# FPGA_CONFIG.net
KiCad netlist of a schematic drawn in Altium Designer
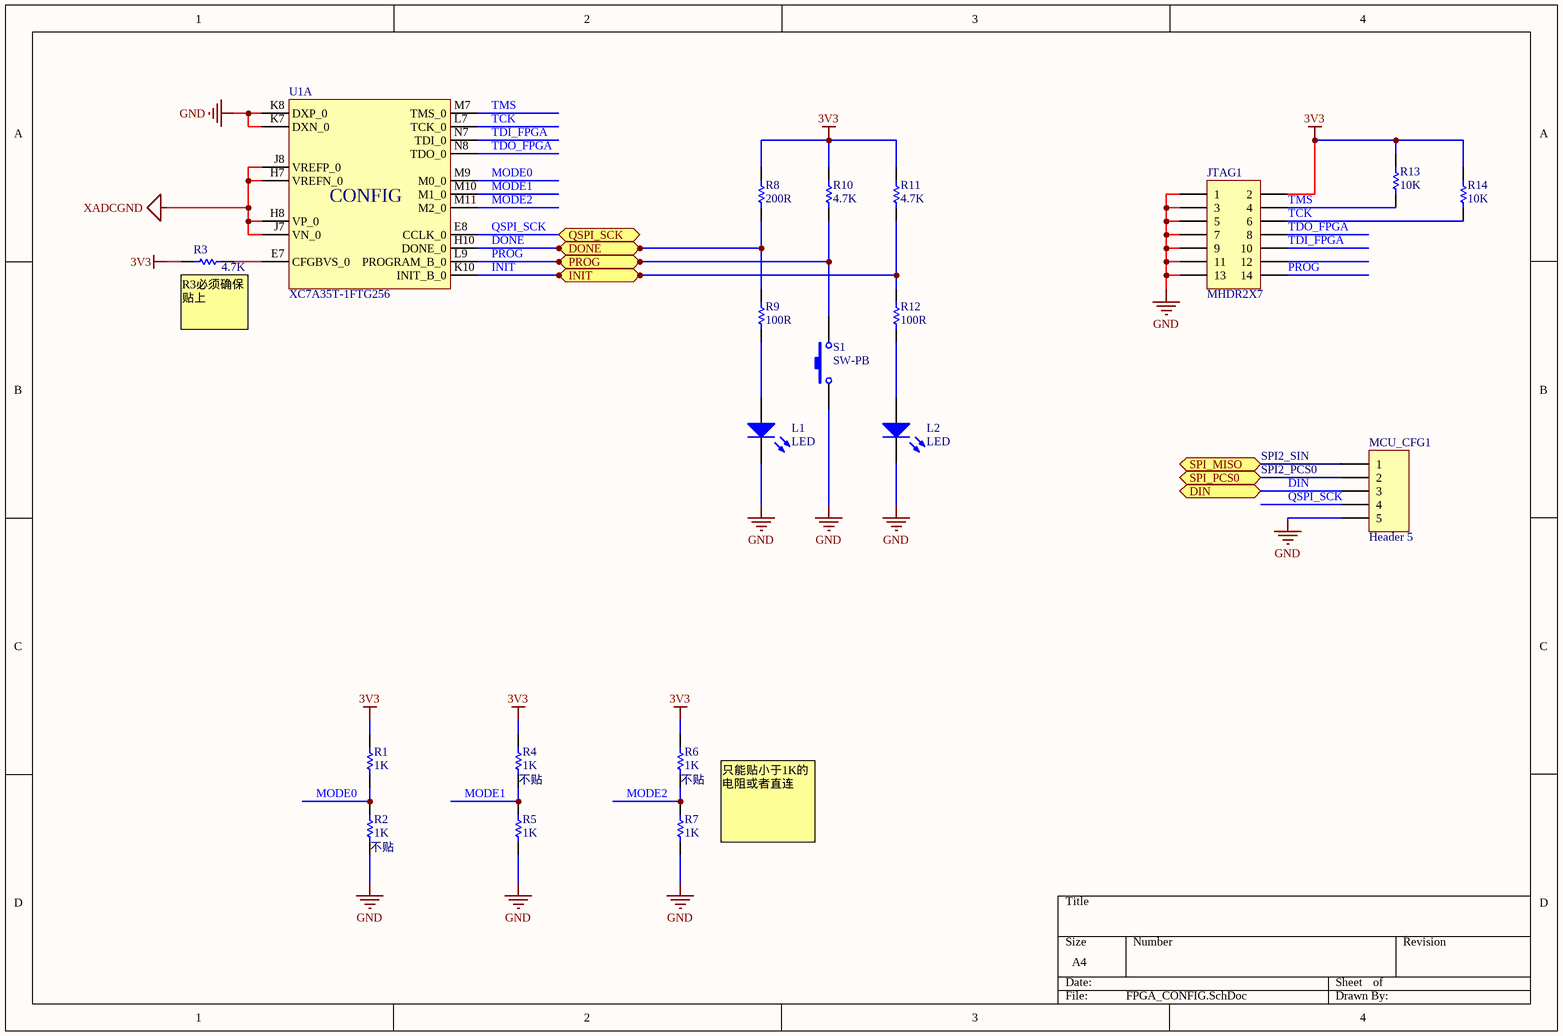
[diagram p0: FPGA_CONFIG.SchDoc]

(export (version "E")
  (design (tool "Eeschema 10.0.6"))
  (components
    (comp (ref "JTAG1")
      (value "MHDR2X7")
      (footprint "Hearder2 7X2")
      (description "Header, 7-Pin, Dual row")
      (fields (field (name "PUBLISHER") "Altium Limited"))
      (libsource (lib "Miscellaneous Connectors") (part "MHDR2X7"))
    )
    (comp (ref "L1") (value "LED") (footprint "1608[0603]") (libsource (lib "Sparks") (part "LED")))
    (comp (ref "L2") (value "LED") (footprint "1608[0603]") (libsource (lib "Sparks") (part "LED")))
    (comp (ref "MCU_CFG1")
      (value "Header 5")
      (footprint "MHDR1X5")
      (description "Header, 5-Pin")
      (fields (field (name "PUBLISHER") "Altium Limited"))
      (libsource (lib "Sparks") (part "Header 5"))
    )
    (comp (ref "R1")
      (value "1K")
      (footprint "1608[0603]")
      (description "贴片电阻")
      (fields (field (name "Comment") "Res") (field (name "PUBLISHER") "Altium Limited"))
      (libsource (lib "Sparks") (part "Res"))
    )
    (comp (ref "R2")
      (value "不贴")
      (footprint "1608[0603]")
      (description "贴片电阻")
      (fields (field (name "ALTIUM_VALUE") "1K") (field (name "PUBLISHER") "Altium Limited"))
      (libsource (lib "Sparks") (part "Res"))
    )
    (comp (ref "R3")
      (value "4.7K")
      (footprint "0402")
      (description "贴片电阻")
      (fields (field (name "Comment") "Res") (field (name "PUBLISHER") "Altium Limited"))
      (libsource (lib "Sparks") (part "Res"))
    )
    (comp (ref "R4")
      (value "不贴")
      (footprint "1608[0603]")
      (description "贴片电阻")
      (fields (field (name "ALTIUM_VALUE") "1K") (field (name "PUBLISHER") "Altium Limited"))
      (libsource (lib "Sparks") (part "Res"))
    )
    (comp (ref "R5")
      (value "1K")
      (footprint "1608[0603]")
      (description "贴片电阻")
      (fields (field (name "Comment") "Res") (field (name "PUBLISHER") "Altium Limited"))
      (libsource (lib "Sparks") (part "Res"))
    )
    (comp (ref "R6")
      (value "不贴")
      (footprint "1608[0603]")
      (description "贴片电阻")
      (fields (field (name "ALTIUM_VALUE") "1K") (field (name "PUBLISHER") "Altium Limited"))
      (libsource (lib "Sparks") (part "Res"))
    )
    (comp (ref "R7")
      (value "1K")
      (footprint "1608[0603]")
      (description "贴片电阻")
      (fields (field (name "Comment") "Res") (field (name "PUBLISHER") "Altium Limited"))
      (libsource (lib "Sparks") (part "Res"))
    )
    (comp (ref "R8")
      (value "200R")
      (footprint "1608[0603]")
      (description "贴片电阻")
      (fields (field (name "Comment") "Res") (field (name "PUBLISHER") "Altium Limited"))
      (libsource (lib "Sparks") (part "Res"))
    )
    (comp (ref "R9")
      (value "100R")
      (footprint "1608[0603]")
      (description "贴片电阻")
      (fields (field (name "Comment") "Res") (field (name "PUBLISHER") "Altium Limited"))
      (libsource (lib "Sparks") (part "Res"))
    )
    (comp (ref "R10")
      (value "4.7K")
      (footprint "1608[0603]")
      (description "贴片电阻")
      (fields (field (name "Comment") "Res") (field (name "PUBLISHER") "Altium Limited"))
      (libsource (lib "Sparks") (part "Res"))
    )
    (comp (ref "R11")
      (value "4.7K")
      (footprint "1608[0603]")
      (description "贴片电阻")
      (fields (field (name "Comment") "Res") (field (name "PUBLISHER") "Altium Limited"))
      (libsource (lib "Sparks") (part "Res"))
    )
    (comp (ref "R12")
      (value "100R")
      (footprint "1608[0603]")
      (description "贴片电阻")
      (fields (field (name "Comment") "Res") (field (name "PUBLISHER") "Altium Limited"))
      (libsource (lib "Sparks") (part "Res"))
    )
    (comp (ref "R13")
      (value "10K")
      (footprint "1608[0603]")
      (description "贴片电阻")
      (fields (field (name "Comment") "Res") (field (name "PUBLISHER") "Altium Limited"))
      (libsource (lib "Sparks") (part "Res"))
    )
    (comp (ref "R14")
      (value "10K")
      (footprint "1608[0603]")
      (description "贴片电阻")
      (fields (field (name "Comment") "Res") (field (name "PUBLISHER") "Altium Limited"))
      (libsource (lib "Sparks") (part "Res"))
    )
    (comp (ref "S1")
      (value "SW-PB")
      (footprint "key 3*4*2")
      (description "Switch")
      (fields (field (name "PUBLISHER") "Altium Limited"))
      (libsource (lib "Miscellaneous Devices") (part "SW-PB"))
    )
    (comp (ref "U1")
      (value "XC7A35T-1FTG256")
      (footprint "BGA100P9X9-81A")
      (libsource (lib "Schlib") (part "XC7A35T-1FTG256"))
    )
  )
  (nets
    (net (code "1") (name "/DIN") (class "Default")
      (node (ref "MCU_CFG1") (pin "3") (pinfunction "3_3") (pintype "passive"))
    )
    (net (code "2") (name "/DONE") (class "Default")
      (node (ref "R8") (pin "1") (pinfunction "1_1") (pintype "passive"))
      (node (ref "R9") (pin "2") (pinfunction "2_2") (pintype "passive"))
      (node (ref "U1") (pin "H10") (pinfunction "DONE_0_H10") (pintype "passive"))
    )
    (net (code "3") (name "/INIT") (class "Default")
      (node (ref "R11") (pin "1") (pinfunction "1_1") (pintype "passive"))
      (node (ref "R12") (pin "2") (pinfunction "2_2") (pintype "passive"))
      (node (ref "U1") (pin "K10") (pinfunction "INIT_B_0_K10") (pintype "passive"))
    )
    (net (code "4") (name "/MODE0") (class "Default")
      (node (ref "R1") (pin "1") (pinfunction "1_1") (pintype "passive"))
      (node (ref "R2") (pin "2") (pinfunction "2_2") (pintype "passive"))
      (node (ref "U1") (pin "M9") (pinfunction "M0_0_M9") (pintype "passive"))
    )
    (net (code "5") (name "/MODE1") (class "Default")
      (node (ref "R4") (pin "1") (pinfunction "1_1") (pintype "passive"))
      (node (ref "R5") (pin "2") (pinfunction "2_2") (pintype "passive"))
      (node (ref "U1") (pin "M10") (pinfunction "M1_0_M10") (pintype "passive"))
    )
    (net (code "6") (name "/MODE2") (class "Default")
      (node (ref "R6") (pin "1") (pinfunction "1_1") (pintype "passive"))
      (node (ref "R7") (pin "2") (pinfunction "2_2") (pintype "passive"))
      (node (ref "U1") (pin "M11") (pinfunction "M2_0_M11") (pintype "passive"))
    )
    (net (code "7") (name "/PROG") (class "Default")
      (node (ref "JTAG1") (pin "14") (pinfunction "14_14") (pintype "passive"))
      (node (ref "R10") (pin "1") (pinfunction "1_1") (pintype "passive"))
      (node (ref "S1") (pin "2") (pinfunction "2_2") (pintype "passive"))
      (node (ref "U1") (pin "L9") (pinfunction "PROGRAM_B_0_L9") (pintype "passive"))
    )
    (net (code "8") (name "/QSPI_SCK") (class "Default")
      (node (ref "MCU_CFG1") (pin "4") (pinfunction "4_4") (pintype "passive"))
      (node (ref "U1") (pin "E8") (pinfunction "CCLK_0_E8") (pintype "passive"))
    )
    (net (code "9") (name "/SPI2_PCS0") (class "Default")
      (node (ref "MCU_CFG1") (pin "2") (pinfunction "2_2") (pintype "passive"))
    )
    (net (code "10") (name "/SPI2_SIN") (class "Default")
      (node (ref "MCU_CFG1") (pin "1") (pinfunction "1_1") (pintype "passive"))
    )
    (net (code "11") (name "/TCK") (class "Default")
      (node (ref "JTAG1") (pin "6") (pinfunction "6_6") (pintype "passive"))
      (node (ref "R14") (pin "1") (pinfunction "1_1") (pintype "passive"))
      (node (ref "U1") (pin "L7") (pinfunction "TCK_0_L7") (pintype "passive"))
    )
    (net (code "12") (name "/TDI_FPGA") (class "Default")
      (node (ref "JTAG1") (pin "10") (pinfunction "10_10") (pintype "passive"))
      (node (ref "U1") (pin "N7") (pinfunction "TDI_0_N7") (pintype "passive"))
    )
    (net (code "13") (name "/TDO_FPGA") (class "Default")
      (node (ref "JTAG1") (pin "8") (pinfunction "8_8") (pintype "passive"))
      (node (ref "U1") (pin "N8") (pinfunction "TDO_0_N8") (pintype "passive"))
    )
    (net (code "14") (name "/TMS") (class "Default")
      (node (ref "JTAG1") (pin "4") (pinfunction "4_4") (pintype "passive"))
      (node (ref "R13") (pin "1") (pinfunction "1_1") (pintype "passive"))
      (node (ref "U1") (pin "M7") (pinfunction "TMS_0_M7") (pintype "passive"))
    )
    (net (code "15") (name "3V3") (class "Default")
      (node (ref "JTAG1") (pin "2") (pinfunction "2_2") (pintype "passive"))
      (node (ref "R1") (pin "2") (pinfunction "2_2") (pintype "passive"))
      (node (ref "R10") (pin "2") (pinfunction "2_2") (pintype "passive"))
      (node (ref "R11") (pin "2") (pinfunction "2_2") (pintype "passive"))
      (node (ref "R13") (pin "2") (pinfunction "2_2") (pintype "passive"))
      (node (ref "R14") (pin "2") (pinfunction "2_2") (pintype "passive"))
      (node (ref "R3") (pin "1") (pinfunction "1_1") (pintype "passive"))
      (node (ref "R4") (pin "2") (pinfunction "2_2") (pintype "passive"))
      (node (ref "R6") (pin "2") (pinfunction "2_2") (pintype "passive"))
      (node (ref "R8") (pin "2") (pinfunction "2_2") (pintype "passive"))
    )
    (net (code "16") (name "GND") (class "Default")
      (node (ref "JTAG1") (pin "1") (pinfunction "1_1") (pintype "passive"))
      (node (ref "JTAG1") (pin "11") (pinfunction "11_11") (pintype "passive"))
      (node (ref "JTAG1") (pin "13") (pinfunction "13_13") (pintype "passive"))
      (node (ref "JTAG1") (pin "3") (pinfunction "3_3") (pintype "passive"))
      (node (ref "JTAG1") (pin "5") (pinfunction "5_5") (pintype "passive"))
      (node (ref "JTAG1") (pin "7") (pinfunction "7_7") (pintype "passive"))
      (node (ref "JTAG1") (pin "9") (pinfunction "9_9") (pintype "passive"))
      (node (ref "L1") (pin "2") (pinfunction "K_2") (pintype "passive"))
      (node (ref "L2") (pin "2") (pinfunction "K_2") (pintype "passive"))
      (node (ref "MCU_CFG1") (pin "5") (pinfunction "5_5") (pintype "passive"))
      (node (ref "R2") (pin "1") (pinfunction "1_1") (pintype "passive"))
      (node (ref "R5") (pin "1") (pinfunction "1_1") (pintype "passive"))
      (node (ref "R7") (pin "1") (pinfunction "1_1") (pintype "passive"))
      (node (ref "S1") (pin "1") (pinfunction "1_1") (pintype "passive"))
      (node (ref "U1") (pin "K7") (pinfunction "DXN_0_K7") (pintype "passive"))
      (node (ref "U1") (pin "K8") (pinfunction "DXP_0_K8") (pintype "passive"))
    )
    (net (code "17") (name "Net-(L1-A)") (class "Default")
      (node (ref "L1") (pin "1") (pinfunction "A_1") (pintype "passive"))
      (node (ref "R9") (pin "1") (pinfunction "1_1") (pintype "passive"))
    )
    (net (code "18") (name "Net-(L2-A)") (class "Default")
      (node (ref "L2") (pin "1") (pinfunction "A_1") (pintype "passive"))
      (node (ref "R12") (pin "1") (pinfunction "1_1") (pintype "passive"))
    )
    (net (code "19") (name "Net-(U1A-CFGBVS_0)") (class "Default")
      (node (ref "R3") (pin "2") (pinfunction "2_2") (pintype "passive"))
      (node (ref "U1") (pin "E7") (pinfunction "CFGBVS_0_E7") (pintype "passive"))
    )
    (net (code "20") (name "XADCGND") (class "Default")
      (node (ref "U1") (pin "H7") (pinfunction "VREFN_0_H7") (pintype "passive"))
      (node (ref "U1") (pin "H8") (pinfunction "VP_0_H8") (pintype "passive"))
      (node (ref "U1") (pin "J7") (pinfunction "VN_0_J7") (pintype "passive"))
      (node (ref "U1") (pin "J8") (pinfunction "VREFP_0_J8") (pintype "passive"))
    )
    (net (code "21") (name "unconnected-(JTAG1-Pad12)") (class "Default")
      (node (ref "JTAG1") (pin "12") (pinfunction "12_12") (pintype "passive"))
    )
  )
)
